# MCU_V2.net
KiCad netlist of a schematic drawn in Altium Designer
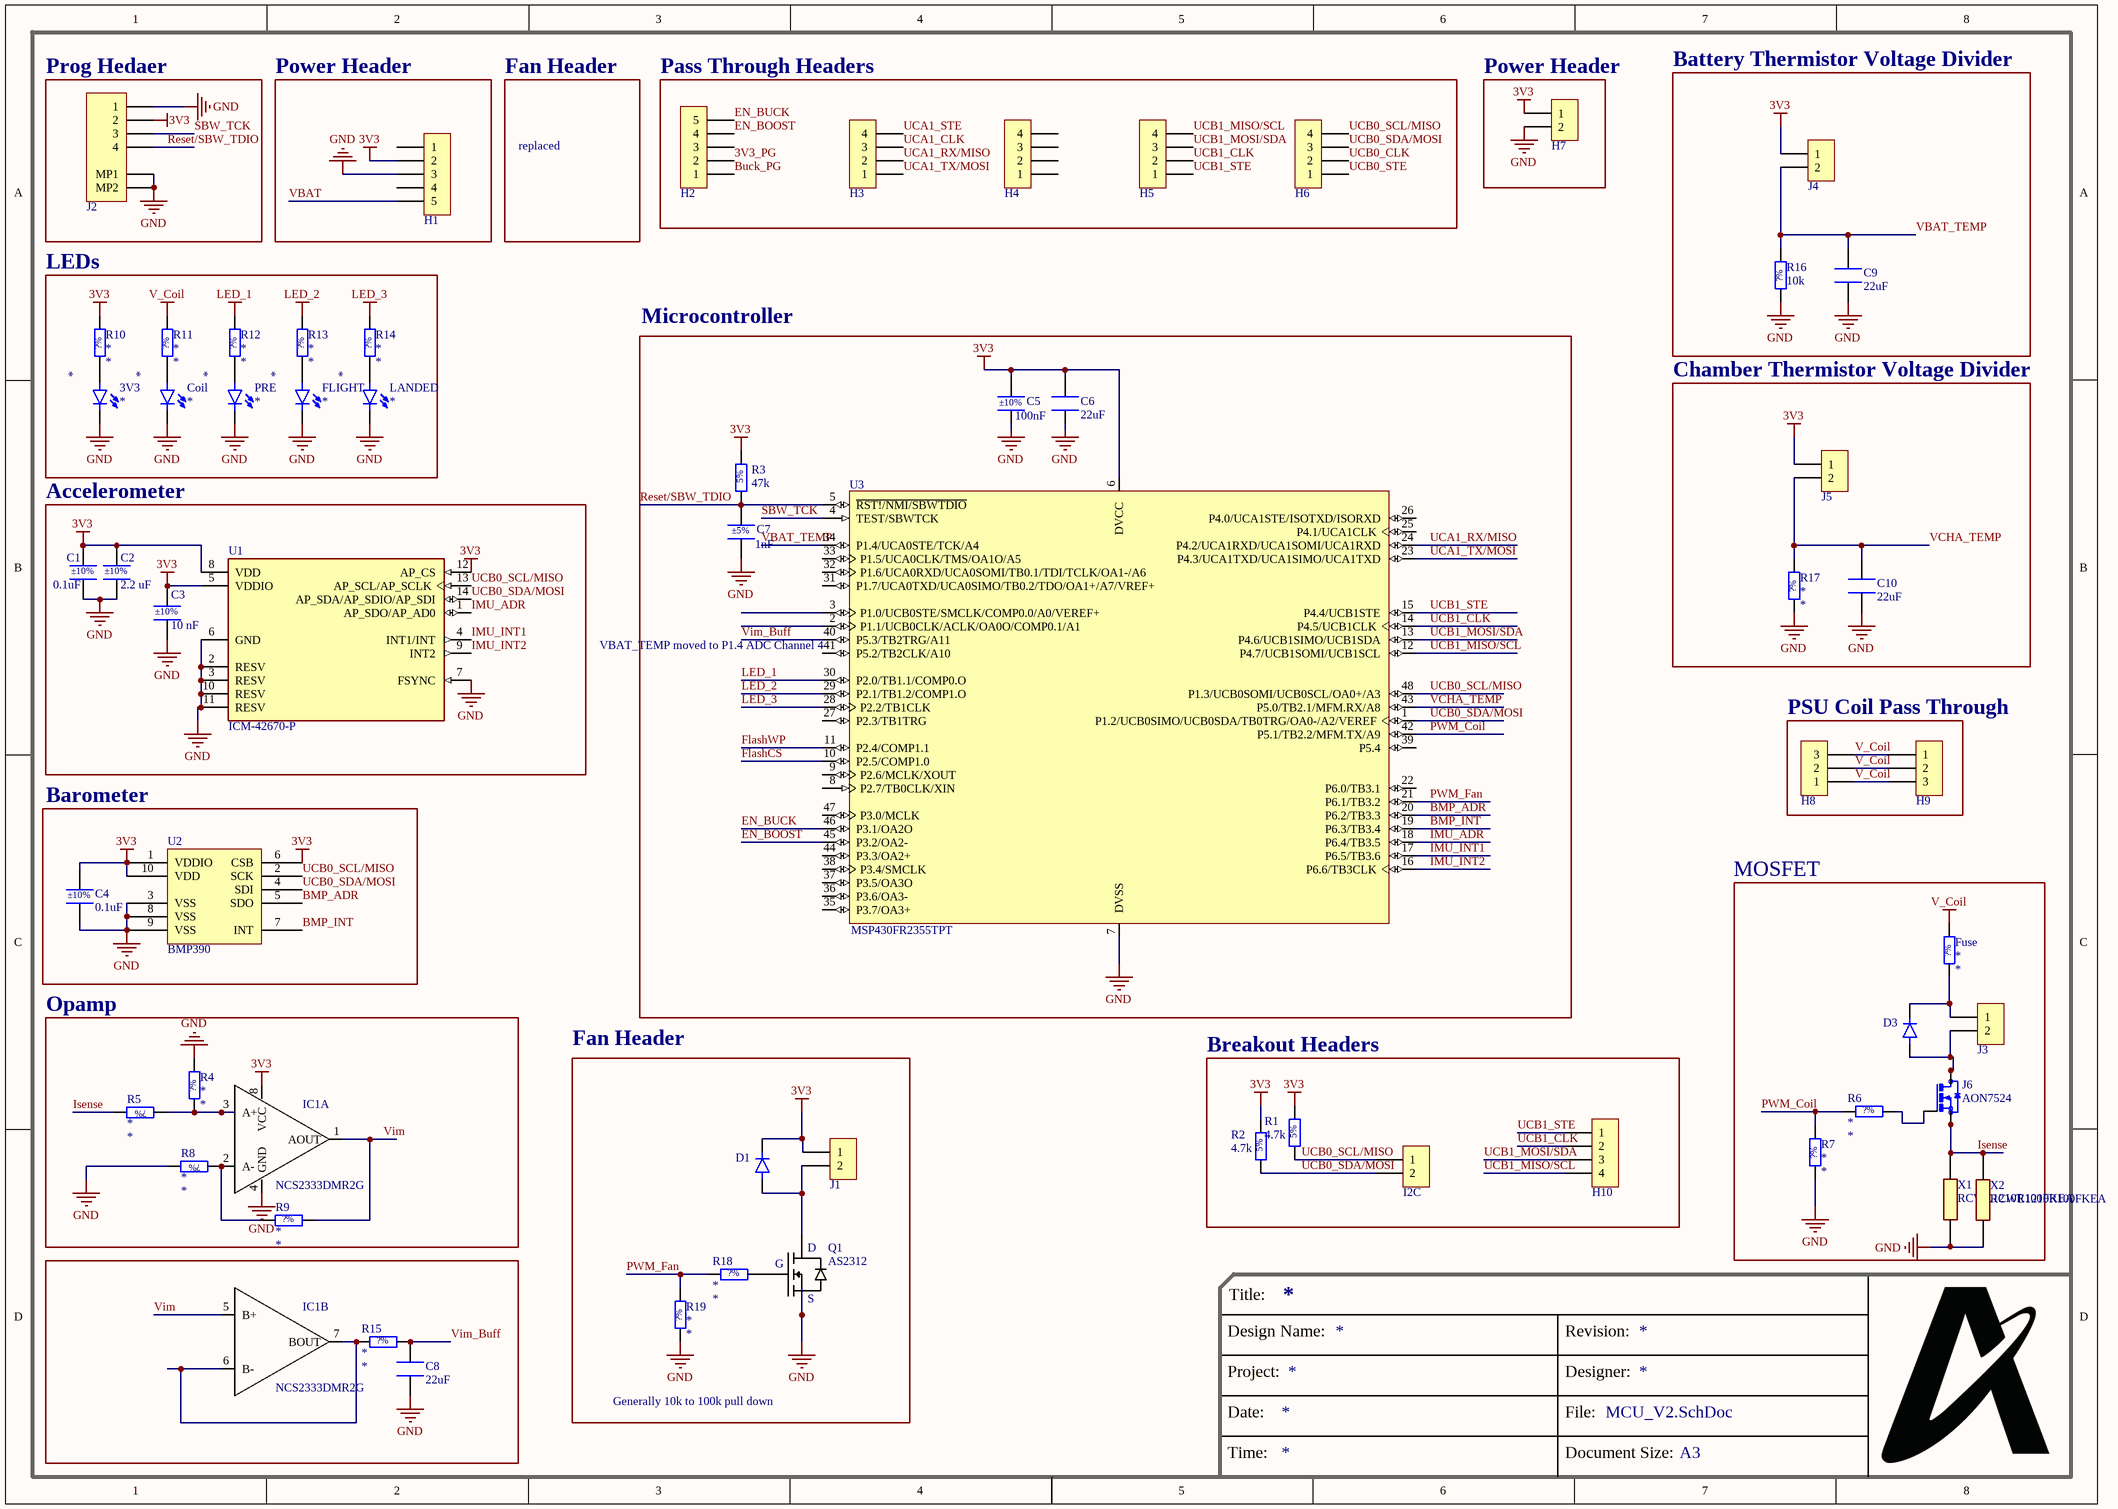
[diagram p0: MCU_V2.SchDoc]

(export (version "E")
  (design (tool "Eeschema 10.0.6"))
  (components
    (comp (ref "3V3")
      (value "LTST-C190 Series")
      (footprint "APSS Prototype Parts:LED_0603_1608M_0.80mm")
      (description "Diode - LED, 0603")
      (fields
        (field (name "APSS STANDARD PART") "APSS Standard")
        (field (name "MF PART NO.") "*")
        (field (name "COLOUR") "*")
      )
      (libsource (lib "APSS Prototype Parts") (part "LTST-C190 Series"))
    )
    (comp (ref "C1")
      (value "0.1uF")
      (footprint "APSS Generic Components:CAPACITOR_0805_2012M-70N")
      (description "Generic Capacitor")
      (fields (field (name "TOLERANCE") "±10%") (field (name "MF PART NO.") "C0805C104K5RAC7800"))
      (libsource (lib "APSS Generic Components") (part "Generic Capacitor"))
    )
    (comp (ref "C2")
      (value "2.2 uF")
      (footprint "APSS Generic Components:CAPACITOR_0805_2012M-70N")
      (description "Generic Capacitor")
      (fields (field (name "TOLERANCE") "±10%") (field (name "MF PART NO.") "C0805C104K5RAC7800"))
      (libsource (lib "APSS Generic Components") (part "Generic Capacitor"))
    )
    (comp (ref "C3")
      (value "10 nF")
      (footprint "APSS Generic Components:CAPACITOR_0805_2012M-70N")
      (description "Generic Capacitor")
      (fields (field (name "TOLERANCE") "±10%") (field (name "MF PART NO.") "C0805C104K5RAC7800"))
      (libsource (lib "APSS Generic Components") (part "Generic Capacitor"))
    )
    (comp (ref "C4")
      (value "0.1uF")
      (footprint "APSS Generic Components:CAPACITOR_0805_2012M-70N")
      (description "Generic Capacitor")
      (fields (field (name "TOLERANCE") "±10%") (field (name "MF PART NO.") "C0805C104K5RAC7800"))
      (libsource (lib "APSS Generic Components") (part "Generic Capacitor"))
    )
    (comp (ref "C5")
      (value "100nF")
      (footprint "APSS Generic Components:CAPACITOR_0805_2012M-70N")
      (description "Generic Capacitor")
      (fields (field (name "TOLERANCE") "±10%") (field (name "MF PART NO.") "C0805C104K5RAC7800"))
      (libsource (lib "General Components") (part "Generic Capacitor"))
    )
    (comp (ref "C6")
      (value "22uF")
      (footprint "APSS Prototype Parts:CAPACITOR_0805_2012M-70N")
      (description "Passive - Capacitor, X5R, 22uF Max, 6.3V, 0805 (2012 Metric), ±20%, -55°C ~ 85°C. 8.8uF @ 5V")
      (fields (field (name "TOLERANCE") "±20%") (field (name "MF PART NO.") "C0805C226M9PACTU"))
      (libsource (lib "APSS Prototype Parts") (part "C0805C226M9PACTU"))
    )
    (comp (ref "C7")
      (value "1nF")
      (footprint "APSS Generic Components:CAPACITOR_0805_2012M-70N")
      (description "Generic Capacitor")
      (fields (field (name "TOLERANCE") "±5%") (field (name "MF PART NO.") "399-C0805C102J5GAC7800CT-ND"))
      (libsource (lib "APSS Generic Components") (part "Generic Capacitor"))
    )
    (comp (ref "C8")
      (value "22uF")
      (footprint "APSS Prototype Parts:CAPACITOR_0805_2012M-70N")
      (description "Passive - Capacitor, X5R, 22uF Max, 6.3V, 0805 (2012 Metric), ±20%, -55°C ~ 85°C. 8.8uF @ 5V")
      (fields (field (name "TOLERANCE") "±20%") (field (name "MF PART NO.") "C0805C226M9PACTU"))
      (libsource (lib "APSS Prototype Parts") (part "C0805C226M9PACTU"))
    )
    (comp (ref "C9")
      (value "22uF")
      (footprint "APSS Prototype Parts:CAPACITOR_0805_2012M-70N")
      (description "Passive - Capacitor, X5R, 22uF Max, 6.3V, 0805 (2012 Metric), ±20%, -55°C ~ 85°C. 8.8uF @ 5V")
      (fields (field (name "TOLERANCE") "±20%") (field (name "MF PART NO.") "C0805C226M9PACTU"))
      (libsource (lib "APSS Prototype Parts") (part "C0805C226M9PACTU"))
    )
    (comp (ref "C10")
      (value "22uF")
      (footprint "APSS Prototype Parts:CAPACITOR_0805_2012M-70N")
      (description "Passive - Capacitor, X5R, 22uF Max, 6.3V, 0805 (2012 Metric), ±20%, -55°C ~ 85°C. 8.8uF @ 5V")
      (fields (field (name "TOLERANCE") "±20%") (field (name "MF PART NO.") "C0805C226M9PACTU"))
      (libsource (lib "APSS Prototype Parts") (part "C0805C226M9PACTU"))
    )
    (comp (ref "Coil")
      (value "LTST-C190 Series")
      (footprint "APSS Prototype Parts:LED_0603_1608M_0.80mm")
      (description "Diode - LED, 0603")
      (fields
        (field (name "APSS STANDARD PART") "APSS Standard")
        (field (name "MF PART NO.") "*")
        (field (name "COLOUR") "*")
      )
      (libsource (lib "APSS Prototype Parts") (part "LTST-C190 Series"))
    )
    (comp (ref "D1")
      (value "1N4148W-TP")
      (footprint "APSS Prototype Parts:SOD123-1.35mm-N")
      (description "Diode - Low Reverse Leakage, 1.25 Vf @ 150 mA, 1 µA Reverse @ 75 V, SOD-123")
      (fields (field (name "APSS STANDARD PART") "APSS Standard"))
      (libsource (lib "APSS Prototype Parts") (part "1N4148W-TP"))
    )
    (comp (ref "D3")
      (value "1N4148W-TP")
      (footprint "APSS Prototype Parts:SOD123-1.35mm-N")
      (description "Diode - Low Reverse Leakage, 1.25 Vf @ 150 mA, 1 µA Reverse @ 75 V, SOD-123")
      (fields (field (name "APSS STANDARD PART") "APSS Standard"))
      (libsource (lib "APSS Prototype Parts") (part "1N4148W-TP"))
    )
    (comp (ref "FLIGHT")
      (value "LTST-C190 Series")
      (footprint "APSS Prototype Parts:LED_0603_1608M_0.80mm")
      (description "Diode - LED, 0603")
      (fields
        (field (name "APSS STANDARD PART") "APSS Standard")
        (field (name "MF PART NO.") "*")
        (field (name "COLOUR") "*")
      )
      (libsource (lib "APSS Prototype Parts") (part "LTST-C190 Series"))
    )
    (comp (ref "Fuse")
      (value "SF-1206HH10M-2")
      (footprint "RESISTOR_1206_3216M_55N")
      (description "Passive - Resistor, Generic")
      (fields
        (field (name "TOLERANCE") "?%")
        (field (name "MF PART NO.") "*")
        (field (name "ALTIUM_VALUE") "*")
      )
      (libsource (lib "APSS Generic Components") (part "Generic Resistor"))
    )
    (comp (ref "H1")
      (value "HDR,2.54mm,1x5")
      (footprint "APSS Connectors:HEADER_2.54MM_1x5PIN")
      (description "Connector - 2.54mm, 1x5-pin")
      (libsource (lib "") (part "HDR,2.54mm,1x5_1"))
    )
    (comp (ref "H2")
      (value "HDR,2.54mm,1x5")
      (footprint "APSS Connectors:HEADER_2.54MM_1x5PIN")
      (description "Connector - 2.54mm, 1x5-pin")
      (libsource (lib "APSS Connectors") (part "HDR,2.54mm,1x5"))
    )
    (comp (ref "H3")
      (value "HDR,2.54mm,1x4")
      (footprint "APSS Connectors:HEADER_2.54MM_1x4PIN")
      (description "Connector - 2.54mm, 1x4-pin")
      (libsource (lib "") (part "HDR,2.54mm,1x4_1"))
    )
    (comp (ref "H4")
      (value "HDR,2.54mm,1x4")
      (footprint "APSS Connectors:HEADER_2.54MM_1x4PIN")
      (description "Connector - 2.54mm, 1x4-pin")
      (libsource (lib "") (part "HDR,2.54mm,1x4_1"))
    )
    (comp (ref "H5")
      (value "HDR,2.54mm,1x4")
      (footprint "APSS Connectors:HEADER_2.54MM_1x4PIN")
      (description "Connector - 2.54mm, 1x4-pin")
      (libsource (lib "") (part "HDR,2.54mm,1x4_1"))
    )
    (comp (ref "H6")
      (value "HDR,2.54mm,1x4")
      (footprint "APSS Connectors:HEADER_2.54MM_1x4PIN")
      (description "Connector - 2.54mm, 1x4-pin")
      (libsource (lib "") (part "HDR,2.54mm,1x4_1"))
    )
    (comp (ref "H7")
      (value "HDR,2.54mm,1x2")
      (footprint "APSS Connectors:HEADER_2.54MM_1x2PIN")
      (description "Connector - 2.54mm, 1x2-pin")
      (libsource (lib "APSS Connectors") (part "HDR,2.54mm,1x2"))
    )
    (comp (ref "H8")
      (value "HDR,2.54mm,1x3")
      (footprint "APSS Connectors:HEADER_2.54MM_1x3PIN")
      (description "Connector - 2.54mm, 1x3-pin")
      (libsource (lib "APSS Connectors") (part "HDR,2.54mm,1x3"))
    )
    (comp (ref "H9")
      (value "HDR,2.54mm,1x3")
      (footprint "APSS Connectors:HEADER_2.54MM_1x3PIN")
      (description "Connector - 2.54mm, 1x3-pin")
      (libsource (lib "") (part "HDR,2.54mm,1x3_1"))
    )
    (comp (ref "H10")
      (value "HDR,2.54mm,1x4")
      (footprint "APSS Connectors:HEADER_2.54MM_1x4PIN")
      (description "Connector - 2.54mm, 1x4-pin")
      (libsource (lib "APSS Connectors") (part "HDR,2.54mm,1x4"))
    )
    (comp (ref "I2C")
      (value "HDR,2.54mm,1x2")
      (footprint "APSS Connectors:HEADER_2.54MM_1x2PIN")
      (description "Connector - 2.54mm, 1x2-pin")
      (libsource (lib "APSS Connectors") (part "HDR,2.54mm,1x2"))
    )
    (comp (ref "IC1")
      (value "NCS2333DMR2G")
      (footprint "*MSOP8")
      (libsource (lib "CTRL Freaks Components") (part "NCS2333DMR2G"))
    )
    (comp (ref "J1")
      (value "0530470210")
      (footprint "APSS Connectors:MOLEX_0530470210")
      (description "Connector - Picoblade 02-pin, TH, STR")
      (fields (field (name "APSS STANDARD PART") "APSS Standard"))
      (libsource (lib "APSS Connectors") (part "0530470210"))
    )
    (comp (ref "J2")
      (value "5015680407")
      (footprint "APSS Connectors:MOLEX_5015680407")
      (description "Connector - Picoclasp  04-pin, SMT, RA")
      (fields (field (name "APSS STANDARD PART") "APSS Standard"))
      (libsource (lib "APSS Connectors") (part "5015680407"))
    )
    (comp (ref "J3")
      (value "0530470210")
      (footprint "APSS Connectors:MOLEX_0530470210")
      (description "Connector - Picoblade 02-pin, TH, STR")
      (fields (field (name "APSS STANDARD PART") "APSS Standard"))
      (libsource (lib "APSS Connectors") (part "0530470210"))
    )
    (comp (ref "J4")
      (value "0530470210")
      (footprint "APSS Connectors:MOLEX_0530470210")
      (description "Connector - Picoblade 02-pin, TH, STR")
      (fields (field (name "APSS STANDARD PART") "APSS Standard"))
      (libsource (lib "APSS Connectors") (part "0530470210"))
    )
    (comp (ref "J5")
      (value "0530470210")
      (footprint "APSS Connectors:MOLEX_0530470210")
      (description "Connector - Picoblade 02-pin, TH, STR")
      (fields (field (name "APSS STANDARD PART") "APSS Standard"))
      (libsource (lib "APSS Connectors") (part "0530470210"))
    )
    (comp (ref "J6")
      (value "AON7524")
      (footprint "CTRL Freaks Components:DFN3X3A-8LEP1")
      (description "N-Channel 30 V 25A (Ta), 28A (Tc) 3.1W (Ta), 32W (Tc) Surface Mount 8-DFN-EP (3x3)")
      (fields (field (name "MF") "Alpha &"))
      (libsource (lib "CTRL Freaks Components") (part "AON7524"))
    )
    (comp (ref "LANDED")
      (value "LTST-C190 Series")
      (footprint "APSS Prototype Parts:LED_0603_1608M_0.80mm")
      (description "Diode - LED, 0603")
      (fields
        (field (name "APSS STANDARD PART") "APSS Standard")
        (field (name "MF PART NO.") "*")
        (field (name "COLOUR") "*")
      )
      (libsource (lib "APSS Prototype Parts") (part "LTST-C190 Series"))
    )
    (comp (ref "PRE")
      (value "LTST-C190 Series")
      (footprint "APSS Prototype Parts:LED_0603_1608M_0.80mm")
      (description "Diode - LED, 0603")
      (fields
        (field (name "APSS STANDARD PART") "APSS Standard")
        (field (name "MF PART NO.") "*")
        (field (name "COLOUR") "*")
      )
      (libsource (lib "APSS Prototype Parts") (part "LTST-C190 Series"))
    )
    (comp (ref "Q1")
      (value "AS2312")
      (footprint "APSS Prototype Parts:SOT23-3N-1.15mm")
      (description "Transistor - MOSFET, N-Channel AS2312")
      (fields (field (name "POWER") "1.2W") (field (name "APSS STANDARD PART") "APSS Standard"))
      (libsource (lib "APSS Prototype Parts") (part "AS2312"))
    )
    (comp (ref "R1")
      (value "4.7k")
      (footprint "APSS Flight Parts:Resistor_0805_2012M-50N")
      (fields
        (field (name "TOLERANCE") "5%")
        (field (name "POWER") "1/8W")
        (field (name "MF PART NO.") "RMCF0805JT4K70")
      )
      (libsource (lib "APSS Prototype Parts") (part "RMCF0805JT Series"))
    )
    (comp (ref "R2")
      (value "4.7k")
      (footprint "APSS Flight Parts:Resistor_0805_2012M-50N")
      (fields
        (field (name "TOLERANCE") "5%")
        (field (name "POWER") "1/8W")
        (field (name "MF PART NO.") "RMCF0805JT4K70")
      )
      (libsource (lib "APSS Prototype Parts") (part "RMCF0805JT Series"))
    )
    (comp (ref "R3")
      (value "47k")
      (footprint "APSS Flight Parts:Resistor_0805_2012M-50N")
      (fields
        (field (name "TOLERANCE") "5%")
        (field (name "POWER") "1/8W")
        (field (name "MF PART NO.") "RMCF0805JT47K0")
      )
      (libsource (lib "APSS Prototype Parts") (part "RMCF0805JT Series"))
    )
    (comp (ref "R4")
      (value "*")
      (footprint "RESISTOR_0805_2012M-50N")
      (description "Passive - Resistor, Generic")
      (fields
        (field (name "TOLERANCE") "?%")
        (field (name "MF PART NO.") "*")
        (field (name "ALTIUM_VALUE") "*")
      )
      (libsource (lib "APSS Generic Components") (part "Generic Resistor"))
    )
    (comp (ref "R5")
      (value "*")
      (footprint "RESISTOR_0805_2012M-50N")
      (description "Passive - Resistor, Generic")
      (fields
        (field (name "TOLERANCE") "?%")
        (field (name "MF PART NO.") "*")
        (field (name "ALTIUM_VALUE") "*")
      )
      (libsource (lib "") (part "Generic Resistor_2"))
    )
    (comp (ref "R6")
      (value "*")
      (footprint "RESISTOR_0805_2012M-50N")
      (description "Passive - Resistor, Generic")
      (fields
        (field (name "TOLERANCE") "?%")
        (field (name "MF PART NO.") "*")
        (field (name "ALTIUM_VALUE") "*")
      )
      (libsource (lib "") (part "Generic Resistor_1"))
    )
    (comp (ref "R7")
      (value "*")
      (footprint "RESISTOR_0805_2012M-50N")
      (description "Passive - Resistor, Generic")
      (fields
        (field (name "TOLERANCE") "?%")
        (field (name "MF PART NO.") "*")
        (field (name "ALTIUM_VALUE") "*")
      )
      (libsource (lib "APSS Generic Components") (part "Generic Resistor"))
    )
    (comp (ref "R8")
      (value "*")
      (footprint "RESISTOR_0805_2012M-50N")
      (description "Passive - Resistor, Generic")
      (fields
        (field (name "TOLERANCE") "?%")
        (field (name "MF PART NO.") "*")
        (field (name "ALTIUM_VALUE") "*")
      )
      (libsource (lib "") (part "Generic Resistor_2"))
    )
    (comp (ref "R9")
      (value "*")
      (footprint "RESISTOR_0805_2012M-50N")
      (description "Passive - Resistor, Generic")
      (fields
        (field (name "TOLERANCE") "?%")
        (field (name "MF PART NO.") "*")
        (field (name "ALTIUM_VALUE") "*")
      )
      (libsource (lib "") (part "Generic Resistor_1"))
    )
    (comp (ref "R10")
      (value "*")
      (footprint "RESISTOR_0805_2012M-50N")
      (description "Passive - Resistor, Generic")
      (fields
        (field (name "TOLERANCE") "?%")
        (field (name "MF PART NO.") "*")
        (field (name "ALTIUM_VALUE") "*")
      )
      (libsource (lib "APSS Generic Components") (part "Generic Resistor"))
    )
    (comp (ref "R11")
      (value "*")
      (footprint "RESISTOR_0805_2012M-50N")
      (description "Passive - Resistor, Generic")
      (fields
        (field (name "TOLERANCE") "?%")
        (field (name "MF PART NO.") "*")
        (field (name "ALTIUM_VALUE") "*")
      )
      (libsource (lib "APSS Generic Components") (part "Generic Resistor"))
    )
    (comp (ref "R12")
      (value "*")
      (footprint "RESISTOR_0805_2012M-50N")
      (description "Passive - Resistor, Generic")
      (fields
        (field (name "TOLERANCE") "?%")
        (field (name "MF PART NO.") "*")
        (field (name "ALTIUM_VALUE") "*")
      )
      (libsource (lib "APSS Generic Components") (part "Generic Resistor"))
    )
    (comp (ref "R13")
      (value "*")
      (footprint "RESISTOR_0805_2012M-50N")
      (description "Passive - Resistor, Generic")
      (fields
        (field (name "TOLERANCE") "?%")
        (field (name "MF PART NO.") "*")
        (field (name "ALTIUM_VALUE") "*")
      )
      (libsource (lib "APSS Generic Components") (part "Generic Resistor"))
    )
    (comp (ref "R14")
      (value "*")
      (footprint "RESISTOR_0805_2012M-50N")
      (description "Passive - Resistor, Generic")
      (fields
        (field (name "TOLERANCE") "?%")
        (field (name "MF PART NO.") "*")
        (field (name "ALTIUM_VALUE") "*")
      )
      (libsource (lib "APSS Generic Components") (part "Generic Resistor"))
    )
    (comp (ref "R15")
      (value "*")
      (footprint "Resistor_0805_2012M-50N")
      (description "Passive - Resistor, Generic")
      (fields
        (field (name "TOLERANCE") "?%")
        (field (name "MF PART NO.") "*")
        (field (name "ALTIUM_VALUE") "*")
      )
      (libsource (lib "") (part "Generic Resistor_1"))
    )
    (comp (ref "R16")
      (value "10k")
      (footprint "RESISTOR_0805_2012M-50N")
      (description "Passive - Resistor, Generic")
      (fields (field (name "TOLERANCE") "?%"))
      (libsource (lib "APSS Generic Components") (part "Generic Resistor"))
    )
    (comp (ref "R17")
      (value "*")
      (footprint "RESISTOR_0805_2012M-50N")
      (description "Passive - Resistor, Generic")
      (fields
        (field (name "TOLERANCE") "?%")
        (field (name "MF PART NO.") "*")
        (field (name "ALTIUM_VALUE") "*")
      )
      (libsource (lib "APSS Generic Components") (part "Generic Resistor"))
    )
    (comp (ref "R18")
      (value "*")
      (footprint "RESISTOR_0805_2012M-50N")
      (description "Passive - Resistor, Generic")
      (fields
        (field (name "TOLERANCE") "?%")
        (field (name "MF PART NO.") "*")
        (field (name "ALTIUM_VALUE") "*")
      )
      (libsource (lib "") (part "Generic Resistor_1"))
    )
    (comp (ref "R19")
      (value "*")
      (footprint "RESISTOR_0805_2012M-50N")
      (description "Passive - Resistor, Generic")
      (fields
        (field (name "TOLERANCE") "?%")
        (field (name "MF PART NO.") "*")
        (field (name "ALTIUM_VALUE") "*")
      )
      (libsource (lib "APSS Generic Components") (part "Generic Resistor"))
    )
    (comp (ref "U1")
      (value "ICM-42670-P")
      (footprint "APSS Prototype Parts:XDCR_ICM-42670-P-EXTENDED_PADS")
      (fields (field (name "APSS STANDARD PART") "APSS Standard"))
      (libsource (lib "APSS Prototype Parts") (part "ICM-42670-P"))
    )
    (comp (ref "U2")
      (value "BMP390")
      (footprint "BMP390")
      (description "Digital Pressure Sensor")
      (fields (field (name "APSS STANDARD PART") "APSS Standard"))
      (libsource (lib "APSS Prototype Parts") (part "BMP390"))
    )
    (comp (ref "U3")
      (value "MSP430FR2355TPT")
      (footprint "APSS Prototype Parts:LQFP_PT_48_N")
      (fields (field (name "APSS STANDARD PART") "APSS Standard"))
      (libsource (lib "APSS Prototype Parts") (part "MSP430FR2355TPT"))
    )
    (comp (ref "X1")
      (value "RCWE1210R100FKEA")
      (footprint "RESC3125X70N")
      (description "Res Thick Film 1210 0.1 Ohm 1% 1W +/-100ppm/C Sulfur Resistant Pad SMD Automotive T/R")
      (fields (field (name "MOUSER PART NUMBER") "71-RCWE1210R100FKEA"))
      (libsource (lib "CTRL Freaks Components") (part "RCWE1210R100FKEA"))
    )
    (comp (ref "X2")
      (value "RCWE1210R100FKEA")
      (footprint "RESC3125X70N")
      (description "Res Thick Film 1210 0.1 Ohm 1% 1W +/-100ppm/C Sulfur Resistant Pad SMD Automotive T/R")
      (fields (field (name "MOUSER PART NUMBER") "71-RCWE1210R100FKEA"))
      (libsource (lib "CTRL Freaks Components") (part "RCWE1210R100FKEA"))
    )
  )
  (nets
    (net (code "1") (name "/3V3_PG") (class "Default")
      (node (ref "H2") (pin "2") (pinfunction "2_2") (pintype "passive"))
    )
    (net (code "2") (name "/BMP_ADR") (class "Default")
      (node (ref "U2") (pin "5") (pinfunction "SDO_5") (pintype "passive"))
      (node (ref "U3") (pin "20") (pinfunction "P6.2/TB3.3_20") (pintype "bidirectional"))
    )
    (net (code "3") (name "/BMP_INT") (class "Default")
      (node (ref "U2") (pin "7") (pinfunction "INT_7") (pintype "passive"))
      (node (ref "U3") (pin "19") (pinfunction "P6.3/TB3.4_19") (pintype "bidirectional"))
    )
    (net (code "4") (name "/Buck_PG") (class "Default")
      (node (ref "H2") (pin "1") (pinfunction "1_1") (pintype "passive"))
    )
    (net (code "5") (name "/EN_BOOST") (class "Default")
      (node (ref "H2") (pin "4") (pinfunction "4_4") (pintype "passive"))
      (node (ref "U3") (pin "45") (pinfunction "P3.2/OA2-_45") (pintype "bidirectional"))
    )
    (net (code "6") (name "/EN_BUCK") (class "Default")
      (node (ref "H2") (pin "5") (pinfunction "5_5") (pintype "passive"))
      (node (ref "U3") (pin "46") (pinfunction "P3.1/OA2O_46") (pintype "bidirectional"))
    )
    (net (code "7") (name "/FlashCS") (class "Default")
      (node (ref "U3") (pin "10") (pinfunction "P2.5/COMP1.0_10") (pintype "bidirectional"))
    )
    (net (code "8") (name "/FlashWP") (class "Default")
      (node (ref "U3") (pin "11") (pinfunction "P2.4/COMP1.1_11") (pintype "bidirectional"))
    )
    (net (code "9") (name "/IMU_ADR") (class "Default")
      (node (ref "U1") (pin "1") (pinfunction "AP_SDO/AP_AD0_1") (pintype "bidirectional"))
      (node (ref "U3") (pin "18") (pinfunction "P6.4/TB3.5_18") (pintype "bidirectional"))
    )
    (net (code "10") (name "/IMU_INT1") (class "Default")
      (node (ref "U1") (pin "4") (pinfunction "INT1/INT_4") (pintype "output"))
      (node (ref "U3") (pin "17") (pinfunction "P6.5/TB3.6_17") (pintype "bidirectional"))
    )
    (net (code "11") (name "/IMU_INT2") (class "Default")
      (node (ref "U1") (pin "9") (pinfunction "INT2_9") (pintype "output"))
      (node (ref "U3") (pin "16") (pinfunction "P6.6/TB3CLK_16") (pintype "bidirectional"))
    )
    (net (code "12") (name "/Isense") (class "Default")
      (node (ref "J6") (pin "P$1") (pinfunction "S_P$1") (pintype "passive"))
      (node (ref "J6") (pin "P$2") (pinfunction "S_P$2") (pintype "passive"))
      (node (ref "J6") (pin "P$3") (pinfunction "S_P$3") (pintype "passive"))
      (node (ref "R5") (pin "2") (pinfunction "2_2") (pintype "passive"))
      (node (ref "X1") (pin "2") (pinfunction "2_2") (pintype "passive"))
      (node (ref "X2") (pin "2") (pinfunction "2_2") (pintype "passive"))
    )
    (net (code "13") (name "/PWM_Coil") (class "Default")
      (node (ref "R6") (pin "1") (pinfunction "1_1") (pintype "passive"))
      (node (ref "R7") (pin "2") (pinfunction "2_2") (pintype "passive"))
      (node (ref "U3") (pin "42") (pinfunction "P5.1/TB2.2/MFM.TX/A9_42") (pintype "bidirectional"))
    )
    (net (code "14") (name "/PWM_Fan") (class "Default")
      (node (ref "R18") (pin "1") (pinfunction "1_1") (pintype "passive"))
      (node (ref "R19") (pin "2") (pinfunction "2_2") (pintype "passive"))
      (node (ref "U3") (pin "21") (pinfunction "P6.1/TB3.2_21") (pintype "bidirectional"))
    )
    (net (code "15") (name "/Reset{slash}SBW_TDIO") (class "Default")
      (node (ref "C7") (pin "2") (pinfunction "2_2") (pintype "passive"))
      (node (ref "J2") (pin "4") (pinfunction "4_4") (pintype "passive"))
      (node (ref "R3") (pin "1") (pinfunction "1_1") (pintype "passive"))
      (node (ref "U3") (pin "5") (pinfunction "~{RST!/NMI/SBWTDIO}_5") (pintype "bidirectional"))
    )
    (net (code "16") (name "/SBW_TCK") (class "Default")
      (node (ref "J2") (pin "3") (pinfunction "3_3") (pintype "passive"))
      (node (ref "U3") (pin "4") (pinfunction "TEST/SBWTCK_4") (pintype "input"))
    )
    (net (code "17") (name "/UCA1_CLK") (class "Default")
      (node (ref "H3") (pin "3") (pinfunction "3_3") (pintype "passive"))
    )
    (net (code "18") (name "/UCA1_RX{slash}MISO") (class "Default")
      (node (ref "H3") (pin "2") (pinfunction "2_2") (pintype "passive"))
      (node (ref "U3") (pin "24") (pinfunction "P4.2/UCA1RXD/UCA1SOMI/UCA1RXD_24") (pintype "bidirectional"))
    )
    (net (code "19") (name "/UCA1_STE") (class "Default")
      (node (ref "H3") (pin "4") (pinfunction "4_4") (pintype "passive"))
    )
    (net (code "20") (name "/UCA1_TX{slash}MOSI") (class "Default")
      (node (ref "H3") (pin "1") (pinfunction "1_1") (pintype "passive"))
      (node (ref "U3") (pin "23") (pinfunction "P4.3/UCA1TXD/UCA1SIMO/UCA1TXD_23") (pintype "bidirectional"))
    )
    (net (code "21") (name "/UCB0_CLK") (class "Default")
      (node (ref "H6") (pin "2") (pinfunction "2_2") (pintype "passive"))
    )
    (net (code "22") (name "/UCB0_SCL{slash}MISO") (class "Default")
      (node (ref "H6") (pin "4") (pinfunction "4_4") (pintype "passive"))
      (node (ref "I2C") (pin "1") (pinfunction "1_1") (pintype "passive"))
      (node (ref "R1") (pin "1") (pinfunction "1_1") (pintype "passive"))
      (node (ref "U1") (pin "13") (pinfunction "AP_SCL/AP_SCLK_13") (pintype "input"))
      (node (ref "U2") (pin "2") (pinfunction "SCK_2") (pintype "passive"))
      (node (ref "U3") (pin "48") (pinfunction "P1.3/UCB0SOMI/UCB0SCL/OA0+/A3_48") (pintype "bidirectional"))
    )
    (net (code "23") (name "/UCB0_SDA{slash}MOSI") (class "Default")
      (node (ref "H6") (pin "3") (pinfunction "3_3") (pintype "passive"))
      (node (ref "I2C") (pin "2") (pinfunction "2_2") (pintype "passive"))
      (node (ref "R2") (pin "1") (pinfunction "1_1") (pintype "passive"))
      (node (ref "U1") (pin "14") (pinfunction "AP_SDA/AP_SDIO/AP_SDI_14") (pintype "bidirectional"))
      (node (ref "U2") (pin "4") (pinfunction "SDI_4") (pintype "passive"))
      (node (ref "U3") (pin "1") (pinfunction "P1.2/UCB0SIMO/UCB0SDA/TB0TRG/OA0-/A2/VEREF_1") (pintype "bidirectional"))
    )
    (net (code "24") (name "/UCB0_STE") (class "Default")
      (node (ref "H6") (pin "1") (pinfunction "1_1") (pintype "passive"))
    )
    (net (code "25") (name "/UCB1_CLK") (class "Default")
      (node (ref "H10") (pin "2") (pinfunction "2_2") (pintype "passive"))
      (node (ref "H5") (pin "2") (pinfunction "2_2") (pintype "passive"))
      (node (ref "U3") (pin "14") (pinfunction "P4.5/UCB1CLK_14") (pintype "bidirectional"))
    )
    (net (code "26") (name "/UCB1_MISO{slash}SCL") (class "Default")
      (node (ref "H10") (pin "4") (pinfunction "4_4") (pintype "passive"))
      (node (ref "H5") (pin "4") (pinfunction "4_4") (pintype "passive"))
      (node (ref "U3") (pin "12") (pinfunction "P4.7/UCB1SOMI/UCB1SCL_12") (pintype "bidirectional"))
    )
    (net (code "27") (name "/UCB1_MOSI{slash}SDA") (class "Default")
      (node (ref "H10") (pin "3") (pinfunction "3_3") (pintype "passive"))
      (node (ref "H5") (pin "3") (pinfunction "3_3") (pintype "passive"))
      (node (ref "U3") (pin "13") (pinfunction "P4.6/UCB1SIMO/UCB1SDA_13") (pintype "bidirectional"))
    )
    (net (code "28") (name "/UCB1_STE") (class "Default")
      (node (ref "H10") (pin "1") (pinfunction "1_1") (pintype "passive"))
      (node (ref "H5") (pin "1") (pinfunction "1_1") (pintype "passive"))
      (node (ref "U3") (pin "15") (pinfunction "P4.4/UCB1STE_15") (pintype "bidirectional"))
    )
    (net (code "29") (name "/VBAT") (class "Default")
      (node (ref "H1") (pin "5") (pinfunction "5_5") (pintype "passive"))
    )
    (net (code "30") (name "/VBAT_TEMP") (class "Default")
      (node (ref "C9") (pin "2") (pinfunction "2_2") (pintype "passive"))
      (node (ref "J4") (pin "2") (pinfunction "2_2") (pintype "passive"))
      (node (ref "R16") (pin "2") (pinfunction "2_2") (pintype "passive"))
      (node (ref "U3") (pin "34") (pinfunction "P1.4/UCA0STE/TCK/A4_34") (pintype "bidirectional"))
    )
    (net (code "31") (name "/VCHA_TEMP") (class "Default")
      (node (ref "C10") (pin "2") (pinfunction "2_2") (pintype "passive"))
      (node (ref "J5") (pin "2") (pinfunction "2_2") (pintype "passive"))
      (node (ref "R17") (pin "2") (pinfunction "2_2") (pintype "passive"))
      (node (ref "U3") (pin "43") (pinfunction "P5.0/TB2.1/MFM.RX/A8_43") (pintype "bidirectional"))
    )
    (net (code "32") (name "/Vim") (class "Default")
      (node (ref "IC1") (pin "1") (pinfunction "AOUT_1") (pintype "bidirectional"))
      (node (ref "IC1") (pin "5") (pinfunction "B+_5") (pintype "bidirectional"))
      (node (ref "R9") (pin "2") (pinfunction "2_2") (pintype "passive"))
    )
    (net (code "33") (name "/Vim_Buff") (class "Default")
      (node (ref "C8") (pin "2") (pinfunction "2_2") (pintype "passive"))
      (node (ref "R15") (pin "2") (pinfunction "2_2") (pintype "passive"))
      (node (ref "U3") (pin "40") (pinfunction "P5.3/TB2TRG/A11_40") (pintype "bidirectional"))
    )
    (net (code "34") (name "3V3") (class "Default")
      (node (ref "C1") (pin "2") (pinfunction "2_2") (pintype "passive"))
      (node (ref "C2") (pin "2") (pinfunction "2_2") (pintype "passive"))
      (node (ref "C3") (pin "2") (pinfunction "2_2") (pintype "passive"))
      (node (ref "C4") (pin "2") (pinfunction "2_2") (pintype "passive"))
      (node (ref "C5") (pin "2") (pinfunction "2_2") (pintype "passive"))
      (node (ref "C6") (pin "2") (pinfunction "2_2") (pintype "passive"))
      (node (ref "D1") (pin "C") (pinfunction "C_C") (pintype "passive"))
      (node (ref "H1") (pin "2") (pinfunction "2_2") (pintype "passive"))
      (node (ref "H7") (pin "1") (pinfunction "1_1") (pintype "passive"))
      (node (ref "IC1") (pin "8") (pinfunction "VCC_8") (pintype "bidirectional"))
      (node (ref "J1") (pin "1") (pinfunction "1_1") (pintype "passive"))
      (node (ref "J2") (pin "2") (pinfunction "2_2") (pintype "passive"))
      (node (ref "J4") (pin "1") (pinfunction "1_1") (pintype "passive"))
      (node (ref "J5") (pin "1") (pinfunction "1_1") (pintype "passive"))
      (node (ref "R1") (pin "2") (pinfunction "2_2") (pintype "passive"))
      (node (ref "R10") (pin "2") (pinfunction "2_2") (pintype "passive"))
      (node (ref "R2") (pin "2") (pinfunction "2_2") (pintype "passive"))
      (node (ref "R3") (pin "2") (pinfunction "2_2") (pintype "passive"))
      (node (ref "U1") (pin "12") (pinfunction "AP_CS_12") (pintype "input"))
      (node (ref "U1") (pin "5") (pinfunction "VDDIO_5") (pintype "power_in"))
      (node (ref "U1") (pin "8") (pinfunction "VDD_8") (pintype "power_in"))
      (node (ref "U2") (pin "1") (pinfunction "VDDIO_1") (pintype "passive"))
      (node (ref "U2") (pin "10") (pinfunction "VDD_10") (pintype "passive"))
      (node (ref "U2") (pin "6") (pinfunction "CSB_6") (pintype "passive"))
      (node (ref "U3") (pin "6") (pinfunction "DVCC_6") (pintype "power_in"))
    )
    (net (code "35") (name "GND") (class "Default")
      (node (ref "3V3") (pin "C") (pinfunction "C_C") (pintype "passive"))
      (node (ref "C1") (pin "1") (pinfunction "1_1") (pintype "passive"))
      (node (ref "C10") (pin "1") (pinfunction "1_1") (pintype "passive"))
      (node (ref "C2") (pin "1") (pinfunction "1_1") (pintype "passive"))
      (node (ref "C3") (pin "1") (pinfunction "1_1") (pintype "passive"))
      (node (ref "C4") (pin "1") (pinfunction "1_1") (pintype "passive"))
      (node (ref "C5") (pin "1") (pinfunction "1_1") (pintype "passive"))
      (node (ref "C6") (pin "1") (pinfunction "1_1") (pintype "passive"))
      (node (ref "C7") (pin "1") (pinfunction "1_1") (pintype "passive"))
      (node (ref "C8") (pin "1") (pinfunction "1_1") (pintype "passive"))
      (node (ref "C9") (pin "1") (pinfunction "1_1") (pintype "passive"))
      (node (ref "Coil") (pin "C") (pinfunction "C_C") (pintype "passive"))
      (node (ref "FLIGHT") (pin "C") (pinfunction "C_C") (pintype "passive"))
      (node (ref "H1") (pin "3") (pinfunction "3_3") (pintype "passive"))
      (node (ref "H7") (pin "2") (pinfunction "2_2") (pintype "passive"))
      (node (ref "IC1") (pin "4") (pinfunction "GND_4") (pintype "bidirectional"))
      (node (ref "J2") (pin "1") (pinfunction "1_1") (pintype "passive"))
      (node (ref "J2") (pin "MP1") (pinfunction "MP1_MP1") (pintype "passive"))
      (node (ref "J2") (pin "MP2") (pinfunction "MP2_MP2") (pintype "passive"))
      (node (ref "LANDED") (pin "C") (pinfunction "C_C") (pintype "passive"))
      (node (ref "PRE") (pin "C") (pinfunction "C_C") (pintype "passive"))
      (node (ref "Q1") (pin "2") (pinfunction "S_2") (pintype "passive"))
      (node (ref "R16") (pin "1") (pinfunction "1_1") (pintype "passive"))
      (node (ref "R17") (pin "1") (pinfunction "1_1") (pintype "passive"))
      (node (ref "R19") (pin "1") (pinfunction "1_1") (pintype "passive"))
      (node (ref "R4") (pin "2") (pinfunction "2_2") (pintype "passive"))
      (node (ref "R7") (pin "1") (pinfunction "1_1") (pintype "passive"))
      (node (ref "R8") (pin "2") (pinfunction "2_2") (pintype "passive"))
      (node (ref "U1") (pin "10") (pinfunction "RESV_10") (pintype "passive"))
      (node (ref "U1") (pin "11") (pinfunction "RESV_11") (pintype "passive"))
      (node (ref "U1") (pin "2") (pinfunction "RESV_2") (pintype "passive"))
      (node (ref "U1") (pin "3") (pinfunction "RESV_3") (pintype "passive"))
      (node (ref "U1") (pin "6") (pinfunction "GND_6") (pintype "power_in"))
      (node (ref "U1") (pin "7") (pinfunction "FSYNC_7") (pintype "input"))
      (node (ref "U2") (pin "3") (pinfunction "VSS_3") (pintype "passive"))
      (node (ref "U2") (pin "8") (pinfunction "VSS_8") (pintype "passive"))
      (node (ref "U2") (pin "9") (pinfunction "VSS_9") (pintype "passive"))
      (node (ref "U3") (pin "7") (pinfunction "DVSS_7") (pintype "power_in"))
      (node (ref "X1") (pin "1") (pinfunction "1_1") (pintype "passive"))
      (node (ref "X2") (pin "1") (pinfunction "1_1") (pintype "passive"))
    )
    (net (code "36") (name "LED_1") (class "Default")
      (node (ref "R12") (pin "2") (pinfunction "2_2") (pintype "passive"))
      (node (ref "U3") (pin "30") (pinfunction "P2.0/TB1.1/COMP0.O_30") (pintype "bidirectional"))
    )
    (net (code "37") (name "LED_2") (class "Default")
      (node (ref "R13") (pin "2") (pinfunction "2_2") (pintype "passive"))
      (node (ref "U3") (pin "29") (pinfunction "P2.1/TB1.2/COMP1.O_29") (pintype "bidirectional"))
    )
    (net (code "38") (name "LED_3") (class "Default")
      (node (ref "R14") (pin "2") (pinfunction "2_2") (pintype "passive"))
      (node (ref "U3") (pin "28") (pinfunction "P2.2/TB1CLK_28") (pintype "bidirectional"))
    )
    (net (code "39") (name "Net-(3V3-PadA)") (class "Default")
      (node (ref "3V3") (pin "A") (pinfunction "A_A") (pintype "passive"))
      (node (ref "R10") (pin "1") (pinfunction "1_1") (pintype "passive"))
    )
    (net (code "40") (name "Net-(Coil-PadA)") (class "Default")
      (node (ref "Coil") (pin "A") (pinfunction "A_A") (pintype "passive"))
      (node (ref "R11") (pin "1") (pinfunction "1_1") (pintype "passive"))
    )
    (net (code "41") (name "Net-(D3-PadA)") (class "Default")
      (node (ref "D3") (pin "A") (pinfunction "A_A") (pintype "passive"))
      (node (ref "J3") (pin "2") (pinfunction "2_2") (pintype "passive"))
      (node (ref "J6") (pin "P$10") (pinfunction "D_P$10") (pintype "passive"))
      (node (ref "J6") (pin "P$11") (pinfunction "D_P$11") (pintype "passive"))
      (node (ref "J6") (pin "P$5") (pinfunction "D_P$5") (pintype "passive"))
      (node (ref "J6") (pin "P$6") (pinfunction "D_P$6") (pintype "passive"))
      (node (ref "J6") (pin "P$7") (pinfunction "D_P$7") (pintype "passive"))
      (node (ref "J6") (pin "P$8") (pinfunction "D_P$8") (pintype "passive"))
      (node (ref "J6") (pin "P$9") (pinfunction "D_P$9") (pintype "passive"))
    )
    (net (code "42") (name "Net-(D3-PadC)") (class "Default")
      (node (ref "D3") (pin "C") (pinfunction "C_C") (pintype "passive"))
      (node (ref "Fuse") (pin "1") (pinfunction "1_1") (pintype "passive"))
      (node (ref "J3") (pin "1") (pinfunction "1_1") (pintype "passive"))
    )
    (net (code "43") (name "Net-(FLIGHT-PadA)") (class "Default")
      (node (ref "FLIGHT") (pin "A") (pinfunction "A_A") (pintype "passive"))
      (node (ref "R13") (pin "1") (pinfunction "1_1") (pintype "passive"))
    )
    (net (code "44") (name "Net-(IC1A-A+)") (class "Default")
      (node (ref "IC1") (pin "3") (pinfunction "A+_3") (pintype "bidirectional"))
      (node (ref "R4") (pin "1") (pinfunction "1_1") (pintype "passive"))
      (node (ref "R5") (pin "1") (pinfunction "1_1") (pintype "passive"))
    )
    (net (code "45") (name "Net-(IC1A-A-)") (class "Default")
      (node (ref "IC1") (pin "2") (pinfunction "A-_2") (pintype "bidirectional"))
      (node (ref "R8") (pin "1") (pinfunction "1_1") (pintype "passive"))
      (node (ref "R9") (pin "1") (pinfunction "1_1") (pintype "passive"))
    )
    (net (code "46") (name "Net-(IC1B-B-)") (class "Default")
      (node (ref "IC1") (pin "6") (pinfunction "B-_6") (pintype "bidirectional"))
      (node (ref "IC1") (pin "7") (pinfunction "BOUT_7") (pintype "bidirectional"))
      (node (ref "R15") (pin "1") (pinfunction "1_1") (pintype "passive"))
    )
    (net (code "47") (name "Net-(J6-G)") (class "Default")
      (node (ref "J6") (pin "P$4") (pinfunction "G_P$4") (pintype "passive"))
      (node (ref "R6") (pin "2") (pinfunction "2_2") (pintype "passive"))
    )
    (net (code "48") (name "Net-(LANDED-PadA)") (class "Default")
      (node (ref "LANDED") (pin "A") (pinfunction "A_A") (pintype "passive"))
      (node (ref "R14") (pin "1") (pinfunction "1_1") (pintype "passive"))
    )
    (net (code "49") (name "Net-(PRE-PadA)") (class "Default")
      (node (ref "PRE") (pin "A") (pinfunction "A_A") (pintype "passive"))
      (node (ref "R12") (pin "1") (pinfunction "1_1") (pintype "passive"))
    )
    (net (code "50") (name "Net-(Q1-D)") (class "Default")
      (node (ref "D1") (pin "A") (pinfunction "A_A") (pintype "passive"))
      (node (ref "J1") (pin "2") (pinfunction "2_2") (pintype "passive"))
      (node (ref "Q1") (pin "3") (pinfunction "D_3") (pintype "passive"))
    )
    (net (code "51") (name "Net-(Q1-G)") (class "Default")
      (node (ref "Q1") (pin "1") (pinfunction "G_1") (pintype "passive"))
      (node (ref "R18") (pin "2") (pinfunction "2_2") (pintype "passive"))
    )
    (net (code "52") (name "V_Coil") (class "Default")
      (node (ref "Fuse") (pin "2") (pinfunction "2_2") (pintype "passive"))
      (node (ref "H8") (pin "1") (pinfunction "1_1") (pintype "passive"))
      (node (ref "H8") (pin "2") (pinfunction "2_2") (pintype "passive"))
      (node (ref "H8") (pin "3") (pinfunction "3_3") (pintype "passive"))
      (node (ref "H9") (pin "1") (pinfunction "1_1") (pintype "passive"))
      (node (ref "H9") (pin "2") (pinfunction "2_2") (pintype "passive"))
      (node (ref "H9") (pin "3") (pinfunction "3_3") (pintype "passive"))
      (node (ref "R11") (pin "2") (pinfunction "2_2") (pintype "passive"))
    )
    (net (code "53") (name "unconnected-(H1-Pad1)") (class "Default")
      (node (ref "H1") (pin "1") (pinfunction "1_1") (pintype "passive"))
    )
    (net (code "54") (name "unconnected-(H1-Pad4)") (class "Default")
      (node (ref "H1") (pin "4") (pinfunction "4_4") (pintype "passive"))
    )
    (net (code "55") (name "unconnected-(H2-Pad3)") (class "Default")
      (node (ref "H2") (pin "3") (pinfunction "3_3") (pintype "passive"))
    )
    (net (code "56") (name "unconnected-(H4-Pad1)") (class "Default")
      (node (ref "H4") (pin "1") (pinfunction "1_1") (pintype "passive"))
    )
    (net (code "57") (name "unconnected-(H4-Pad2)") (class "Default")
      (node (ref "H4") (pin "2") (pinfunction "2_2") (pintype "passive"))
    )
    (net (code "58") (name "unconnected-(H4-Pad3)") (class "Default")
      (node (ref "H4") (pin "3") (pinfunction "3_3") (pintype "passive"))
    )
    (net (code "59") (name "unconnected-(H4-Pad4)") (class "Default")
      (node (ref "H4") (pin "4") (pinfunction "4_4") (pintype "passive"))
    )
    (net (code "60") (name "unconnected-(U3-P1.0{slash}UCB0STE{slash}SMCLK{slash}COMP0.0{slash}A0{slash}VEREF+-Pad3)") (class "Default")
      (node (ref "U3") (pin "3") (pinfunction "P1.0/UCB0STE/SMCLK/COMP0.0/A0/VEREF+_3") (pintype "bidirectional"))
    )
    (net (code "61") (name "unconnected-(U3-P1.1{slash}UCB0CLK{slash}ACLK{slash}OA0O{slash}COMP0.1{slash}A1-Pad2)") (class "Default")
      (node (ref "U3") (pin "2") (pinfunction "P1.1/UCB0CLK/ACLK/OA0O/COMP0.1/A1_2") (pintype "bidirectional"))
    )
    (net (code "62") (name "unconnected-(U3-P1.5{slash}UCA0CLK{slash}TMS{slash}OA1O{slash}A5-Pad33)") (class "Default")
      (node (ref "U3") (pin "33") (pinfunction "P1.5/UCA0CLK/TMS/OA1O/A5_33") (pintype "bidirectional"))
    )
    (net (code "63") (name "unconnected-(U3-P1.6{slash}UCA0RXD{slash}UCA0SOMI{slash}TB0.1{slash}TDI{slash}TCLK{slash}OA1-{slash}A6-Pad32)") (class "Default")
      (node (ref "U3") (pin "32") (pinfunction "P1.6/UCA0RXD/UCA0SOMI/TB0.1/TDI/TCLK/OA1-/A6_32") (pintype "bidirectional"))
    )
    (net (code "64") (name "unconnected-(U3-P1.7{slash}UCA0TXD{slash}UCA0SIMO{slash}TB0.2{slash}TDO{slash}OA1+{slash}A7{slash}VREF+-Pad31)") (class "Default")
      (node (ref "U3") (pin "31") (pinfunction "P1.7/UCA0TXD/UCA0SIMO/TB0.2/TDO/OA1+/A7/VREF+_31") (pintype "bidirectional"))
    )
    (net (code "65") (name "unconnected-(U3-P2.3{slash}TB1TRG-Pad27)") (class "Default")
      (node (ref "U3") (pin "27") (pinfunction "P2.3/TB1TRG_27") (pintype "bidirectional"))
    )
    (net (code "66") (name "unconnected-(U3-P2.6{slash}MCLK{slash}XOUT-Pad9)") (class "Default")
      (node (ref "U3") (pin "9") (pinfunction "P2.6/MCLK/XOUT_9") (pintype "bidirectional"))
    )
    (net (code "67") (name "unconnected-(U3-P2.7{slash}TB0CLK{slash}XIN-Pad8)") (class "Default")
      (node (ref "U3") (pin "8") (pinfunction "P2.7/TB0CLK/XIN_8") (pintype "input"))
    )
    (net (code "68") (name "unconnected-(U3-P3.0{slash}MCLK-Pad47)") (class "Default")
      (node (ref "U3") (pin "47") (pinfunction "P3.0/MCLK_47") (pintype "bidirectional"))
    )
    (net (code "69") (name "unconnected-(U3-P3.3{slash}OA2+-Pad44)") (class "Default")
      (node (ref "U3") (pin "44") (pinfunction "P3.3/OA2+_44") (pintype "bidirectional"))
    )
    (net (code "70") (name "unconnected-(U3-P3.4{slash}SMCLK-Pad38)") (class "Default")
      (node (ref "U3") (pin "38") (pinfunction "P3.4/SMCLK_38") (pintype "bidirectional"))
    )
    (net (code "71") (name "unconnected-(U3-P3.5{slash}OA3O-Pad37)") (class "Default")
      (node (ref "U3") (pin "37") (pinfunction "P3.5/OA3O_37") (pintype "bidirectional"))
    )
    (net (code "72") (name "unconnected-(U3-P3.6{slash}OA3--Pad36)") (class "Default")
      (node (ref "U3") (pin "36") (pinfunction "P3.6/OA3-_36") (pintype "bidirectional"))
    )
    (net (code "73") (name "unconnected-(U3-P3.7{slash}OA3+-Pad35)") (class "Default")
      (node (ref "U3") (pin "35") (pinfunction "P3.7/OA3+_35") (pintype "bidirectional"))
    )
    (net (code "74") (name "unconnected-(U3-P4.0{slash}UCA1STE{slash}ISOTXD{slash}ISORXD-Pad26)") (class "Default")
      (node (ref "U3") (pin "26") (pinfunction "P4.0/UCA1STE/ISOTXD/ISORXD_26") (pintype "bidirectional"))
    )
    (net (code "75") (name "unconnected-(U3-P4.1{slash}UCA1CLK-Pad25)") (class "Default")
      (node (ref "U3") (pin "25") (pinfunction "P4.1/UCA1CLK_25") (pintype "bidirectional"))
    )
    (net (code "76") (name "unconnected-(U3-P5.2{slash}TB2CLK{slash}A10-Pad41)") (class "Default")
      (node (ref "U3") (pin "41") (pinfunction "P5.2/TB2CLK/A10_41") (pintype "bidirectional"))
    )
    (net (code "77") (name "unconnected-(U3-P5.4-Pad39)") (class "Default")
      (node (ref "U3") (pin "39") (pinfunction "P5.4_39") (pintype "bidirectional"))
    )
    (net (code "78") (name "unconnected-(U3-P6.0{slash}TB3.1-Pad22)") (class "Default")
      (node (ref "U3") (pin "22") (pinfunction "P6.0/TB3.1_22") (pintype "bidirectional"))
    )
  )
)
